# ch340g-esp32.net
KiCad netlist of a schematic drawn in EAGLE
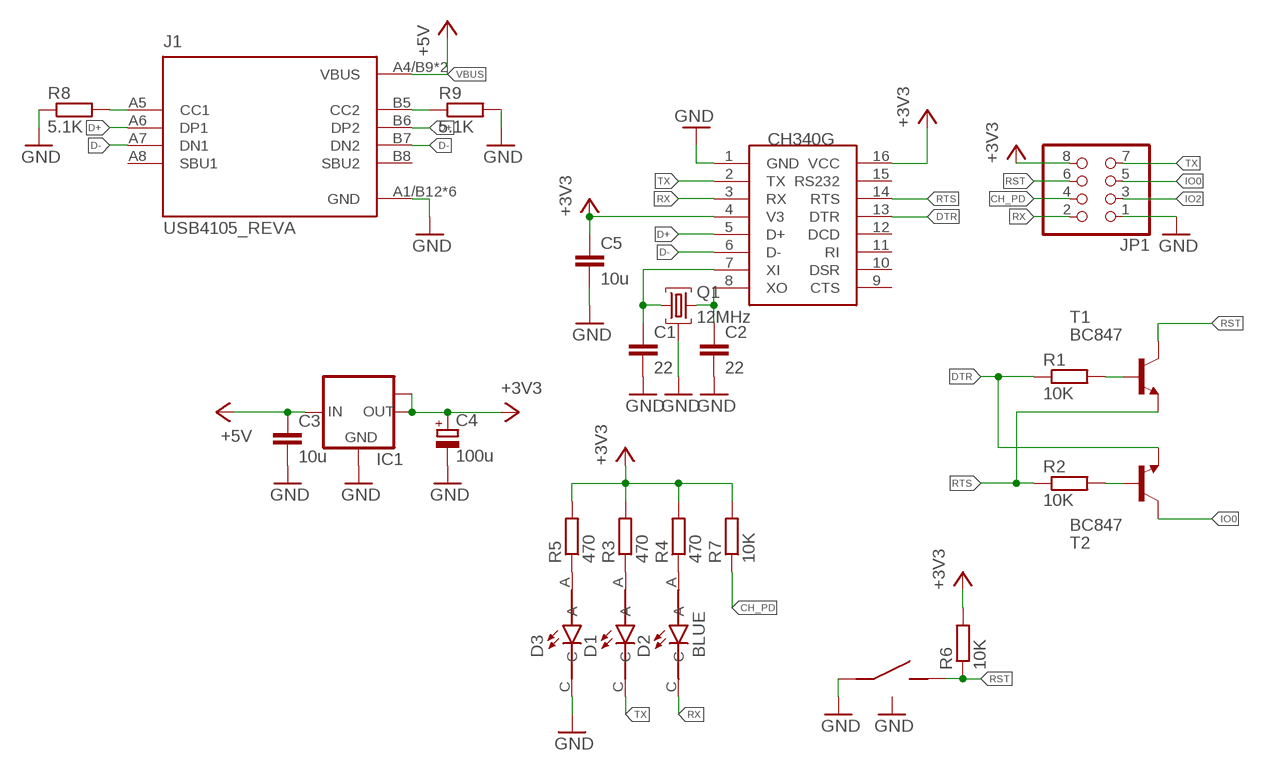
[diagram p0: schematic, sheet 1]

(export (version "E")
  (design (tool "Eeschema 10.0.6"))
  (components
    (comp (ref "BTN1")
      (value "TS36CA-0.7")
      (footprint "eagle-import:SMD")
      (fields (field (name "MF") "SHOU HAN"))
      (libsource (lib "eagle-import") (part "TS36CA-0.7"))
    )
    (comp (ref "C1")
      (value "22")
      (footprint "eagle-import:C0603")
      (libsource (lib "eagle-import") (part "C-EUC0603"))
    )
    (comp (ref "C2")
      (value "22")
      (footprint "eagle-import:C0603")
      (libsource (lib "eagle-import") (part "C-EUC0603"))
    )
    (comp (ref "C3")
      (value "10u")
      (footprint "eagle-import:C0603")
      (libsource (lib "eagle-import") (part "C-EUC0603"))
    )
    (comp (ref "C4")
      (value "100u")
      (footprint "eagle-import:B_3528-21W")
      (libsource (lib "eagle-import") (part "CPOL-EUB/3528-21W"))
    )
    (comp (ref "C5")
      (value "10u")
      (footprint "eagle-import:C0603")
      (libsource (lib "eagle-import") (part "C-EUC0603"))
    )
    (comp (ref "D1")
      (value "BLUE")
      (footprint "eagle-import:LEDC2012X70N")
      (fields (field (name "MF") "Dialight") (field (name "MP") "597-5311-402F"))
      (libsource (lib "eagle-import") (part "597-5311-402F"))
    )
    (comp (ref "D2")
      (value "BLUE")
      (footprint "eagle-import:LEDC2012X70N")
      (fields (field (name "MF") "Dialight") (field (name "MP") "597-5311-402F"))
      (libsource (lib "eagle-import") (part "597-5311-402F"))
    )
    (comp (ref "D3")
      (value "GREEN")
      (footprint "eagle-import:LEDC2012X70N")
      (fields (field (name "MF") "Dialight") (field (name "MP") "597-5311-402F"))
      (libsource (lib "eagle-import") (part "597-5311-402F"))
    )
    (comp (ref "IC1")
      (value "LM1117MPX-3.3")
      (footprint "eagle-import:SOT223")
      (libsource (lib "eagle-import") (part "LM1117MPX-3.3"))
    )
    (comp (ref "J1")
      (value "USB4105_REVA")
      (footprint "eagle-import:GCT_USB4105_REVA")
      (fields (field (name "MF") "Global Connector Technology") (field (name "MP") "USB4105"))
      (libsource (lib "eagle-import") (part "USB4105_REVA"))
    )
    (comp (ref "JP1")
      (value "PINHD-2X4")
      (footprint "eagle-import:2X04")
      (libsource (lib "eagle-import") (part "PINHD-2X4"))
    )
    (comp (ref "Q1")
      (value "12MHz")
      (footprint "eagle-import:SMD3225")
      (fields (field (name "MF") "Yangxing Tech") (field (name "MP") "X322512MSB4SI"))
      (libsource (lib "eagle-import") (part "YSX321SL"))
    )
    (comp (ref "R1")
      (value "10K")
      (footprint "eagle-import:R0603")
      (libsource (lib "eagle-import") (part "R-EU_R0603"))
    )
    (comp (ref "R2")
      (value "10K")
      (footprint "eagle-import:R0603")
      (libsource (lib "eagle-import") (part "R-EU_R0603"))
    )
    (comp (ref "R3")
      (value "470")
      (footprint "eagle-import:R0603")
      (libsource (lib "eagle-import") (part "R-EU_R0603"))
    )
    (comp (ref "R4")
      (value "470")
      (footprint "eagle-import:R0603")
      (libsource (lib "eagle-import") (part "R-EU_R0603"))
    )
    (comp (ref "R5")
      (value "470")
      (footprint "eagle-import:R0603")
      (libsource (lib "eagle-import") (part "R-EU_R0603"))
    )
    (comp (ref "R6")
      (value "10K")
      (footprint "eagle-import:R0603")
      (libsource (lib "eagle-import") (part "R-EU_R0603"))
    )
    (comp (ref "R7")
      (value "10K")
      (footprint "eagle-import:R0603")
      (libsource (lib "eagle-import") (part "R-EU_R0603"))
    )
    (comp (ref "R8")
      (value "5.1K")
      (footprint "eagle-import:R0603")
      (libsource (lib "eagle-import") (part "R-EU_R0603"))
    )
    (comp (ref "R9")
      (value "5.1K")
      (footprint "eagle-import:R0603")
      (libsource (lib "eagle-import") (part "R-EU_R0603"))
    )
    (comp (ref "T1")
      (value "BC847")
      (footprint "eagle-import:SOT23")
      (libsource (lib "eagle-import") (part "BC847"))
    )
    (comp (ref "T2")
      (value "BC847")
      (footprint "eagle-import:SOT23")
      (libsource (lib "eagle-import") (part "BC847"))
    )
    (comp (ref "U1")
      (value "CH340G")
      (footprint "eagle-import:SOIC16")
      (libsource (lib "eagle-import") (part "CH340G"))
    )
  )
  (nets
    (net (code "1") (name "+3V3") (class "Default")
      (node (ref "C4") (pin "+") (pinfunction "+_+") (pintype "passive"))
      (node (ref "C5") (pin "1") (pinfunction "1_1") (pintype "passive"))
      (node (ref "IC1") (pin "2") (pinfunction "OUT_2") (pintype "passive"))
      (node (ref "IC1") (pin "TAB") (pinfunction "OUT1_TAB") (pintype "passive"))
      (node (ref "JP1") (pin "8") (pinfunction "8_8") (pintype "passive"))
      (node (ref "R3") (pin "2") (pinfunction "2_2") (pintype "passive"))
      (node (ref "R4") (pin "2") (pinfunction "2_2") (pintype "passive"))
      (node (ref "R5") (pin "2") (pinfunction "2_2") (pintype "passive"))
      (node (ref "R6") (pin "2") (pinfunction "2_2") (pintype "passive"))
      (node (ref "R7") (pin "2") (pinfunction "2_2") (pintype "passive"))
      (node (ref "U1") (pin "16") (pinfunction "VCC_16") (pintype "bidirectional"))
      (node (ref "U1") (pin "4") (pinfunction "V3_4") (pintype "bidirectional"))
    )
    (net (code "2") (name "CH_PD") (class "Default")
      (node (ref "JP1") (pin "4") (pinfunction "4_4") (pintype "passive"))
      (node (ref "R7") (pin "1") (pinfunction "1_1") (pintype "passive"))
    )
    (net (code "3") (name "D+") (class "Default")
      (node (ref "J1") (pin "A6") (pinfunction "DP1_A6") (pintype "bidirectional"))
      (node (ref "J1") (pin "B6") (pinfunction "DP2_B6") (pintype "bidirectional"))
      (node (ref "U1") (pin "5") (pinfunction "D+_5") (pintype "bidirectional"))
    )
    (net (code "4") (name "D-") (class "Default")
      (node (ref "J1") (pin "A7") (pinfunction "DN1_A7") (pintype "bidirectional"))
      (node (ref "J1") (pin "B7") (pinfunction "DN2_B7") (pintype "bidirectional"))
      (node (ref "U1") (pin "6") (pinfunction "D-_6") (pintype "bidirectional"))
    )
    (net (code "5") (name "DTR") (class "Default")
      (node (ref "R1") (pin "1") (pinfunction "1_1") (pintype "passive"))
      (node (ref "T2") (pin "2") (pinfunction "E_2") (pintype "passive"))
      (node (ref "U1") (pin "13") (pinfunction "DTR_13") (pintype "bidirectional"))
    )
    (net (code "6") (name "GND") (class "Default")
      (node (ref "BTN1") (pin "A") (pinfunction "CASE_A") (pintype "power_in"))
      (node (ref "BTN1") (pin "B") (pinfunction "CASE_B") (pintype "power_in"))
      (node (ref "BTN1") (pin "C") (pinfunction "P$1_C") (pintype "bidirectional"))
      (node (ref "C1") (pin "2") (pinfunction "2_2") (pintype "passive"))
      (node (ref "C2") (pin "2") (pinfunction "2_2") (pintype "passive"))
      (node (ref "C3") (pin "2") (pinfunction "2_2") (pintype "passive"))
      (node (ref "C4") (pin "-") (pinfunction "-_-") (pintype "passive"))
      (node (ref "C5") (pin "2") (pinfunction "2_2") (pintype "passive"))
      (node (ref "D3") (pin "C") (pinfunction "C_C") (pintype "passive"))
      (node (ref "IC1") (pin "1") (pinfunction "GND_1") (pintype "input"))
      (node (ref "J1") (pin "A1/B12") (pinfunction "GND_A1/B12") (pintype "power_in"))
      (node (ref "J1") (pin "B1/A12") (pinfunction "GND_B1/A12") (pintype "power_in"))
      (node (ref "J1") (pin "G1") (pinfunction "GND_G1") (pintype "power_in"))
      (node (ref "J1") (pin "G2") (pinfunction "GND_G2") (pintype "power_in"))
      (node (ref "J1") (pin "G3") (pinfunction "GND_G3") (pintype "power_in"))
      (node (ref "J1") (pin "G4") (pinfunction "GND_G4") (pintype "power_in"))
      (node (ref "JP1") (pin "1") (pinfunction "1_1") (pintype "passive"))
      (node (ref "Q1") (pin "P$2") (pinfunction "CASE_P$2") (pintype "power_in"))
      (node (ref "Q1") (pin "P$4") (pinfunction "CASE_P$4") (pintype "power_in"))
      (node (ref "R8") (pin "1") (pinfunction "1_1") (pintype "passive"))
      (node (ref "R9") (pin "2") (pinfunction "2_2") (pintype "passive"))
      (node (ref "U1") (pin "1") (pinfunction "GND_1") (pintype "bidirectional"))
    )
    (net (code "7") (name "IO0") (class "Default")
      (node (ref "JP1") (pin "5") (pinfunction "5_5") (pintype "passive"))
      (node (ref "T2") (pin "3") (pinfunction "C_3") (pintype "passive"))
    )
    (net (code "8") (name "IO2") (class "Default")
      (node (ref "JP1") (pin "3") (pinfunction "3_3") (pintype "passive"))
    )
    (net (code "9") (name "Net-(D1-PadA)") (class "Default")
      (node (ref "D1") (pin "A") (pinfunction "A_A") (pintype "passive"))
      (node (ref "R3") (pin "1") (pinfunction "1_1") (pintype "passive"))
    )
    (net (code "10") (name "Net-(D2-PadA)") (class "Default")
      (node (ref "D2") (pin "A") (pinfunction "A_A") (pintype "passive"))
      (node (ref "R4") (pin "1") (pinfunction "1_1") (pintype "passive"))
    )
    (net (code "11") (name "Net-(D3-PadA)") (class "Default")
      (node (ref "D3") (pin "A") (pinfunction "A_A") (pintype "passive"))
      (node (ref "R5") (pin "1") (pinfunction "1_1") (pintype "passive"))
    )
    (net (code "12") (name "Net-(J1-CC1)") (class "Default")
      (node (ref "J1") (pin "A5") (pinfunction "CC1_A5") (pintype "bidirectional"))
      (node (ref "R8") (pin "2") (pinfunction "2_2") (pintype "passive"))
    )
    (net (code "13") (name "Net-(J1-CC2)") (class "Default")
      (node (ref "J1") (pin "B5") (pinfunction "CC2_B5") (pintype "bidirectional"))
      (node (ref "R9") (pin "1") (pinfunction "1_1") (pintype "passive"))
    )
    (net (code "14") (name "Net-(Q1-1)") (class "Default")
      (node (ref "C1") (pin "1") (pinfunction "1_1") (pintype "passive"))
      (node (ref "Q1") (pin "P$1") (pinfunction "1_P$1") (pintype "passive"))
      (node (ref "U1") (pin "7") (pinfunction "XI_7") (pintype "bidirectional"))
    )
    (net (code "15") (name "Net-(Q1-2)") (class "Default")
      (node (ref "C2") (pin "1") (pinfunction "1_1") (pintype "passive"))
      (node (ref "Q1") (pin "P$3") (pinfunction "2_P$3") (pintype "passive"))
      (node (ref "U1") (pin "8") (pinfunction "XO_8") (pintype "bidirectional"))
    )
    (net (code "16") (name "Net-(T1-B)") (class "Default")
      (node (ref "R1") (pin "2") (pinfunction "2_2") (pintype "passive"))
      (node (ref "T1") (pin "1") (pinfunction "B_1") (pintype "passive"))
    )
    (net (code "17") (name "Net-(T2-B)") (class "Default")
      (node (ref "R2") (pin "2") (pinfunction "2_2") (pintype "passive"))
      (node (ref "T2") (pin "1") (pinfunction "B_1") (pintype "passive"))
    )
    (net (code "18") (name "RST") (class "Default")
      (node (ref "BTN1") (pin "D") (pinfunction "P$2_D") (pintype "bidirectional"))
      (node (ref "JP1") (pin "6") (pinfunction "6_6") (pintype "passive"))
      (node (ref "R6") (pin "1") (pinfunction "1_1") (pintype "passive"))
      (node (ref "T1") (pin "3") (pinfunction "C_3") (pintype "passive"))
    )
    (net (code "19") (name "RTS") (class "Default")
      (node (ref "R2") (pin "1") (pinfunction "1_1") (pintype "passive"))
      (node (ref "T1") (pin "2") (pinfunction "E_2") (pintype "passive"))
      (node (ref "U1") (pin "14") (pinfunction "RTS_14") (pintype "bidirectional"))
    )
    (net (code "20") (name "RX") (class "Default")
      (node (ref "D2") (pin "C") (pinfunction "C_C") (pintype "passive"))
      (node (ref "JP1") (pin "2") (pinfunction "2_2") (pintype "passive"))
      (node (ref "U1") (pin "3") (pinfunction "RX_3") (pintype "bidirectional"))
    )
    (net (code "21") (name "TX") (class "Default")
      (node (ref "D1") (pin "C") (pinfunction "C_C") (pintype "passive"))
      (node (ref "JP1") (pin "7") (pinfunction "7_7") (pintype "passive"))
      (node (ref "U1") (pin "2") (pinfunction "TX_2") (pintype "bidirectional"))
    )
    (net (code "22") (name "VBUS") (class "Default")
      (node (ref "C3") (pin "1") (pinfunction "1_1") (pintype "passive"))
      (node (ref "IC1") (pin "3") (pinfunction "IN_3") (pintype "input"))
      (node (ref "J1") (pin "A4/B9") (pinfunction "VBUS_A4/B9") (pintype "power_in"))
      (node (ref "J1") (pin "B4/A9") (pinfunction "VBUS_B4/A9") (pintype "power_in"))
    )
    (net (code "23") (name "unconnected-(J1-SBU1-PadA8)") (class "Default")
      (node (ref "J1") (pin "A8") (pinfunction "SBU1_A8") (pintype "bidirectional"))
    )
    (net (code "24") (name "unconnected-(J1-SBU2-PadB8)") (class "Default")
      (node (ref "J1") (pin "B8") (pinfunction "SBU2_B8") (pintype "bidirectional"))
    )
    (net (code "25") (name "unconnected-(U1-CTS-Pad9)") (class "Default")
      (node (ref "U1") (pin "9") (pinfunction "CTS_9") (pintype "bidirectional"))
    )
    (net (code "26") (name "unconnected-(U1-DCD-Pad12)") (class "Default")
      (node (ref "U1") (pin "12") (pinfunction "DCD_12") (pintype "bidirectional"))
    )
    (net (code "27") (name "unconnected-(U1-DSR-Pad10)") (class "Default")
      (node (ref "U1") (pin "10") (pinfunction "DSR_10") (pintype "bidirectional"))
    )
    (net (code "28") (name "unconnected-(U1-RI-Pad11)") (class "Default")
      (node (ref "U1") (pin "11") (pinfunction "RI_11") (pintype "bidirectional"))
    )
    (net (code "29") (name "unconnected-(U1-RS232-Pad15)") (class "Default")
      (node (ref "U1") (pin "15") (pinfunction "RS232_15") (pintype "bidirectional"))
    )
  )
)
